# PL-N823-01_Analog_Breakout.net
KiCad netlist of a schematic drawn in EAGLE
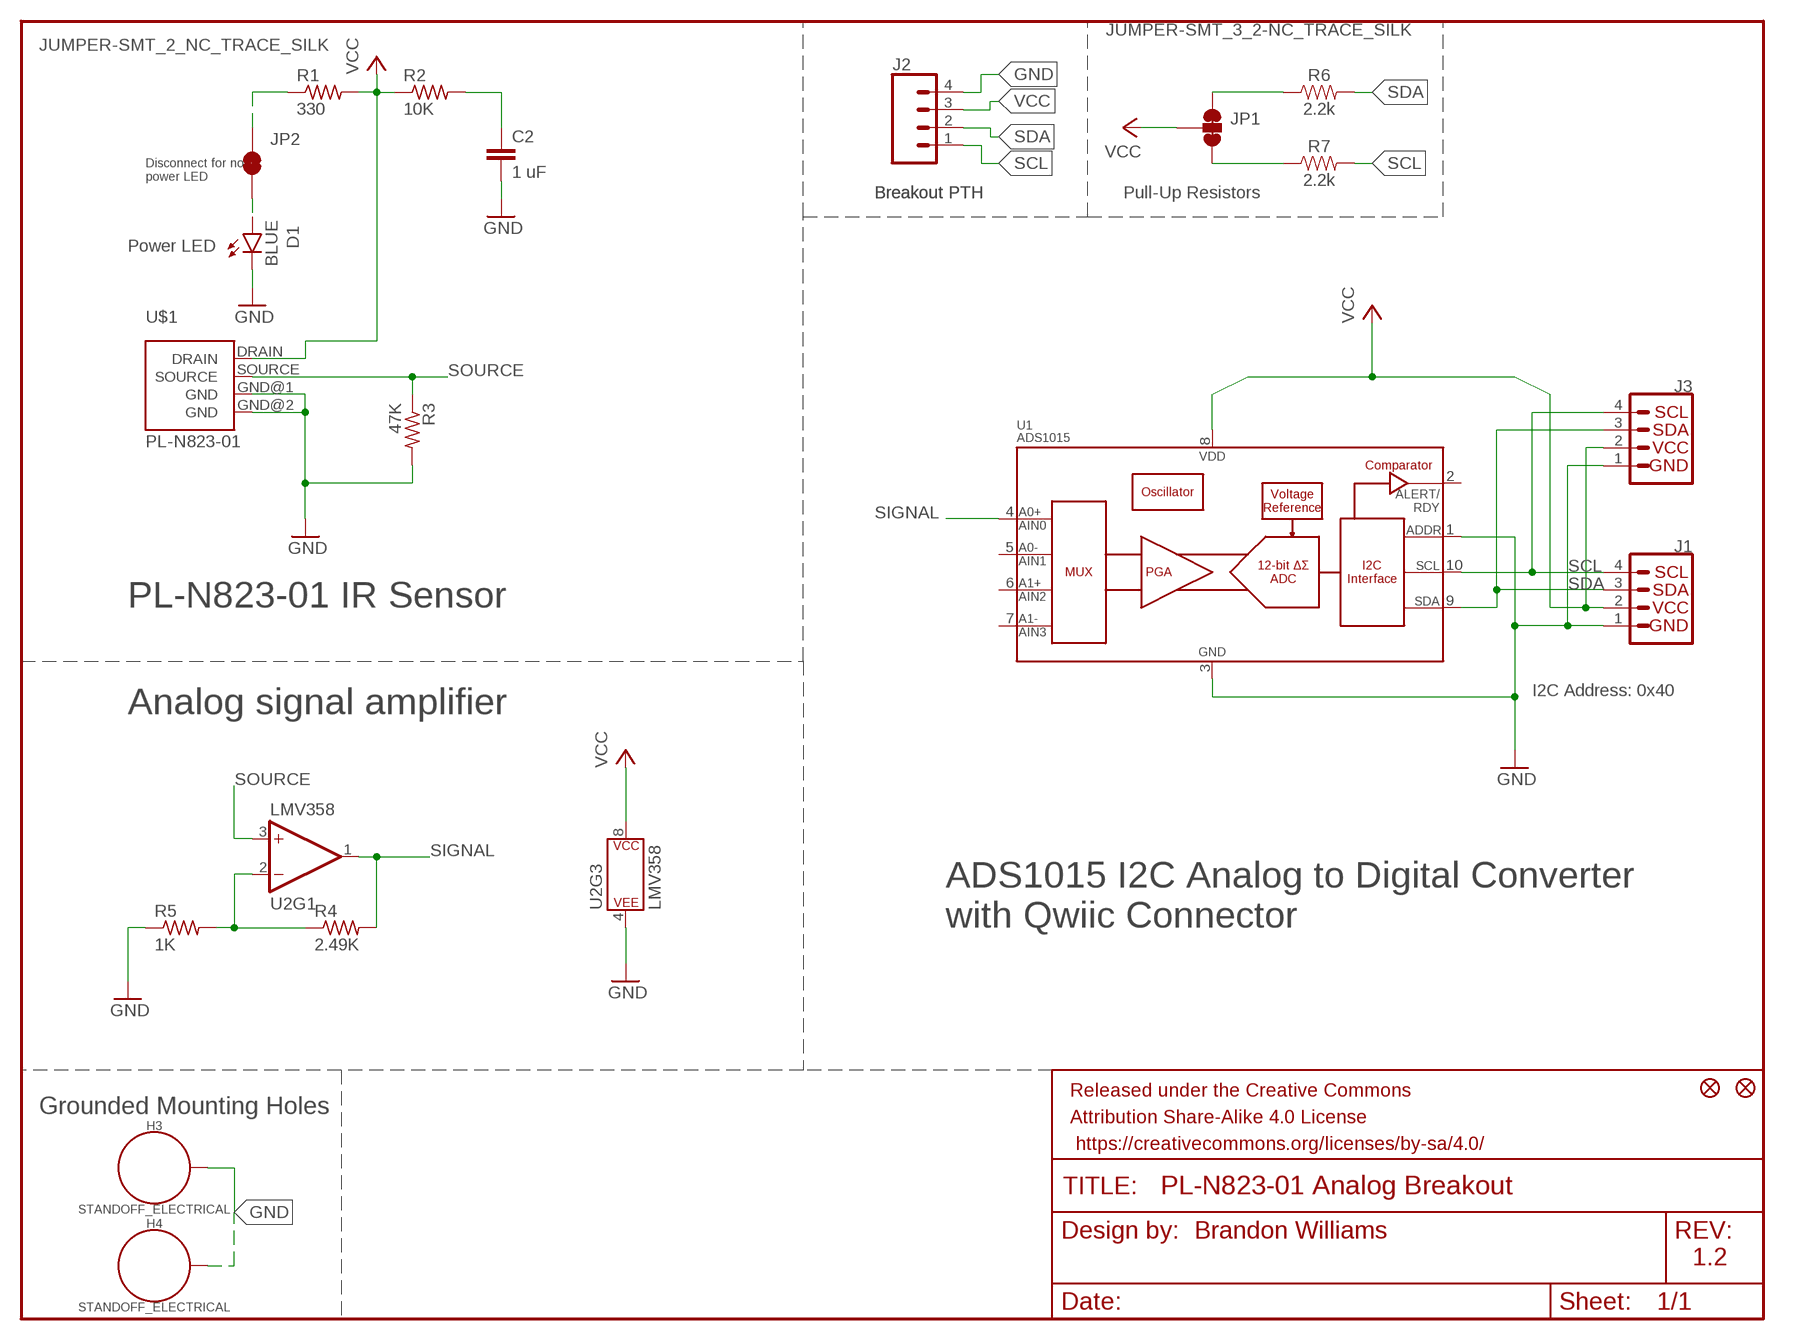
[diagram p0: schematic, sheet 1]

(export (version "E")
  (design (tool "Eeschema 10.0.6"))
  (components
    (comp (ref "C2")
      (value "1 uF")
      (footprint "eagle-import:C0603")
      (libsource (lib "eagle-import") (part "C-EUC0603"))
    )
    (comp (ref "D1")
      (value "BLUE")
      (footprint "eagle-import:LED-0603")
      (libsource (lib "eagle-import") (part "LED-BLUE0603"))
    )
    (comp (ref "FD1")
      (value "FIDUCIALUFIDUCIAL")
      (footprint "eagle-import:FIDUCIAL-MICRO")
      (libsource (lib "eagle-import") (part "FIDUCIALUFIDUCIAL"))
    )
    (comp (ref "FD2")
      (value "FIDUCIALUFIDUCIAL")
      (footprint "eagle-import:FIDUCIAL-MICRO")
      (libsource (lib "eagle-import") (part "FIDUCIALUFIDUCIAL"))
    )
    (comp (ref "FRAME1")
      (value "FRAME-LETTERNO_PACKAGE")
      (footprint "eagle-import:DUMMY")
      (fields (field (name "DESIGNER") "Nobody"))
      (libsource (lib "eagle-import") (part "FRAME-LETTERNO_PACKAGE"))
    )
    (comp (ref "H3")
      (value "STANDOFF_ELECTRICAL")
      (footprint "eagle-import:STANDOFF-ELECTRICAL")
      (libsource (lib "eagle-import") (part "STANDOFF_ELECTRICAL"))
    )
    (comp (ref "H4")
      (value "STANDOFF_ELECTRICAL")
      (footprint "eagle-import:STANDOFF-ELECTRICAL")
      (libsource (lib "eagle-import") (part "STANDOFF_ELECTRICAL"))
    )
    (comp (ref "J1")
      (value "QWIIC_CONNECTORJS-1MM")
      (footprint "eagle-import:1X04_1MM_RA")
      (libsource (lib "eagle-import") (part "QWIIC_CONNECTORJS-1MM"))
    )
    (comp (ref "J2")
      (value "CONN_041X04_NO_SILK")
      (footprint "eagle-import:1X04_NO_SILK")
      (libsource (lib "eagle-import") (part "CONN_041X04_NO_SILK"))
    )
    (comp (ref "J3")
      (value "QWIIC_CONNECTORJS-1MM")
      (footprint "eagle-import:1X04_1MM_RA")
      (libsource (lib "eagle-import") (part "QWIIC_CONNECTORJS-1MM"))
    )
    (comp (ref "JP1")
      (value "JUMPER-SMT_3_2-NC_TRACE_SILK")
      (footprint "eagle-import:SMT-JUMPER_3_2-NC_TRACE_SILK")
      (libsource (lib "eagle-import") (part "JUMPER-SMT_3_2-NC_TRACE_SILK"))
    )
    (comp (ref "JP2")
      (value "JUMPER-SMT_2_NC_TRACE_SILK")
      (footprint "eagle-import:SMT-JUMPER_2_NC_TRACE_SILK")
      (libsource (lib "eagle-import") (part "JUMPER-SMT_2_NC_TRACE_SILK"))
    )
    (comp (ref "R1")
      (value "330")
      (footprint "eagle-import:R0603")
      (libsource (lib "eagle-import") (part "R-US_R0603"))
    )
    (comp (ref "R2")
      (value "10K")
      (footprint "eagle-import:R0603")
      (libsource (lib "eagle-import") (part "R-US_R0603"))
    )
    (comp (ref "R3")
      (value "47K")
      (footprint "eagle-import:R0603")
      (libsource (lib "eagle-import") (part "R-US_R0603"))
    )
    (comp (ref "R4")
      (value "2.49K")
      (footprint "eagle-import:R0603")
      (libsource (lib "eagle-import") (part "R-US_R0603"))
    )
    (comp (ref "R5")
      (value "1K")
      (footprint "eagle-import:R0603")
      (libsource (lib "eagle-import") (part "R-US_R0603"))
    )
    (comp (ref "R6")
      (value "2.2k")
      (footprint "eagle-import:0603")
      (libsource (lib "eagle-import") (part "2.2KOHM-0603-1/10W-1%"))
    )
    (comp (ref "R7")
      (value "2.2k")
      (footprint "eagle-import:0603")
      (libsource (lib "eagle-import") (part "2.2KOHM-0603-1/10W-1%"))
    )
    (comp (ref "U$1")
      (value "PL-N823-01")
      (footprint "eagle-import:PL-N823-01")
      (libsource (lib "eagle-import") (part "PL-N823-01"))
    )
    (comp (ref "U1")
      (value "ADS1015")
      (footprint "eagle-import:MSOP10")
      (libsource (lib "eagle-import") (part "ADS1015"))
    )
    (comp (ref "U2")
      (value "LMV358")
      (footprint "eagle-import:SO08")
      (libsource (lib "eagle-import") (part "LMV358SOIC"))
    )
  )
  (nets
    (net (code "1") (name "/SIGNAL") (class "Default")
      (node (ref "R4") (pin "2") (pinfunction "2_2") (pintype "passive"))
      (node (ref "U1") (pin "4") (pinfunction "AIN0_4") (pintype "bidirectional"))
      (node (ref "U2") (pin "1") (pinfunction "OUT_1") (pintype "output"))
    )
    (net (code "2") (name "/SOURCE") (class "Default")
      (node (ref "R3") (pin "1") (pinfunction "1_1") (pintype "passive"))
      (node (ref "U$1") (pin "SOURCE") (pinfunction "SOURCE_SOURCE") (pintype "output"))
      (node (ref "U2") (pin "3") (pinfunction "+IN_3") (pintype "input"))
    )
    (net (code "3") (name "GND") (class "Default")
      (node (ref "C2") (pin "2") (pinfunction "2_2") (pintype "passive"))
      (node (ref "D1") (pin "C") (pinfunction "C_C") (pintype "passive"))
      (node (ref "H3") (pin "P1") (pinfunction "P$1_P1") (pintype "bidirectional"))
      (node (ref "H4") (pin "P1") (pinfunction "P$1_P1") (pintype "bidirectional"))
      (node (ref "J1") (pin "1") (pinfunction "GND_1") (pintype "power_in"))
      (node (ref "J2") (pin "4") (pinfunction "4_4") (pintype "passive"))
      (node (ref "J3") (pin "1") (pinfunction "GND_1") (pintype "power_in"))
      (node (ref "R3") (pin "2") (pinfunction "2_2") (pintype "passive"))
      (node (ref "R5") (pin "1") (pinfunction "1_1") (pintype "passive"))
      (node (ref "U$1") (pin "GND@1") (pinfunction "GND_GND@1") (pintype "power_in"))
      (node (ref "U$1") (pin "GND@2") (pinfunction "GND_GND@2") (pintype "power_in"))
      (node (ref "U1") (pin "1") (pinfunction "ADDR_1") (pintype "bidirectional"))
      (node (ref "U1") (pin "3") (pinfunction "VSS_3") (pintype "bidirectional"))
      (node (ref "U2") (pin "4") (pinfunction "P$V-_4") (pintype "bidirectional"))
    )
    (net (code "4") (name "Net-(C2-Pad1)") (class "Default")
      (node (ref "C2") (pin "1") (pinfunction "1_1") (pintype "passive"))
      (node (ref "R2") (pin "2") (pinfunction "2_2") (pintype "passive"))
    )
    (net (code "5") (name "Net-(D1-PadA)") (class "Default")
      (node (ref "D1") (pin "A") (pinfunction "A_A") (pintype "passive"))
      (node (ref "JP2") (pin "2") (pinfunction "2_2") (pintype "passive"))
    )
    (net (code "6") (name "Net-(JP1-Pad1)") (class "Default")
      (node (ref "JP1") (pin "1") (pinfunction "1_1") (pintype "passive"))
      (node (ref "R6") (pin "1") (pinfunction "1_1") (pintype "passive"))
    )
    (net (code "7") (name "Net-(JP1-Pad3)") (class "Default")
      (node (ref "JP1") (pin "3") (pinfunction "3_3") (pintype "passive"))
      (node (ref "R7") (pin "1") (pinfunction "1_1") (pintype "passive"))
    )
    (net (code "8") (name "Net-(JP2-Pad1)") (class "Default")
      (node (ref "JP2") (pin "1") (pinfunction "1_1") (pintype "passive"))
      (node (ref "R1") (pin "1") (pinfunction "1_1") (pintype "passive"))
    )
    (net (code "9") (name "Net-(U2A--IN)") (class "Default")
      (node (ref "R4") (pin "1") (pinfunction "1_1") (pintype "passive"))
      (node (ref "R5") (pin "2") (pinfunction "2_2") (pintype "passive"))
      (node (ref "U2") (pin "2") (pinfunction "-IN_2") (pintype "input"))
    )
    (net (code "10") (name "SCL") (class "Default")
      (node (ref "J1") (pin "4") (pinfunction "SCL_4") (pintype "passive"))
      (node (ref "J2") (pin "1") (pinfunction "1_1") (pintype "passive"))
      (node (ref "J3") (pin "4") (pinfunction "SCL_4") (pintype "passive"))
      (node (ref "R7") (pin "2") (pinfunction "2_2") (pintype "passive"))
      (node (ref "U1") (pin "10") (pinfunction "SCL_10") (pintype "bidirectional"))
    )
    (net (code "11") (name "SDA") (class "Default")
      (node (ref "J1") (pin "3") (pinfunction "SDA_3") (pintype "passive"))
      (node (ref "J2") (pin "2") (pinfunction "2_2") (pintype "passive"))
      (node (ref "J3") (pin "3") (pinfunction "SDA_3") (pintype "passive"))
      (node (ref "R6") (pin "2") (pinfunction "2_2") (pintype "passive"))
      (node (ref "U1") (pin "9") (pinfunction "SDA_9") (pintype "bidirectional"))
    )
    (net (code "12") (name "VCC") (class "Default")
      (node (ref "J1") (pin "2") (pinfunction "VCC_2") (pintype "power_in"))
      (node (ref "J2") (pin "3") (pinfunction "3_3") (pintype "passive"))
      (node (ref "J3") (pin "2") (pinfunction "VCC_2") (pintype "power_in"))
      (node (ref "JP1") (pin "2") (pinfunction "2_2") (pintype "passive"))
      (node (ref "R1") (pin "2") (pinfunction "2_2") (pintype "passive"))
      (node (ref "R2") (pin "1") (pinfunction "1_1") (pintype "passive"))
      (node (ref "U$1") (pin "DRAIN") (pinfunction "DRAIN_DRAIN") (pintype "input"))
      (node (ref "U1") (pin "8") (pinfunction "VDD_8") (pintype "bidirectional"))
      (node (ref "U2") (pin "8") (pinfunction "P$V+_8") (pintype "bidirectional"))
    )
    (net (code "13") (name "unconnected-(U1-AIN1-Pad5)") (class "Default")
      (node (ref "U1") (pin "5") (pinfunction "AIN1_5") (pintype "bidirectional"))
    )
    (net (code "14") (name "unconnected-(U1-AIN2-Pad6)") (class "Default")
      (node (ref "U1") (pin "6") (pinfunction "AIN2_6") (pintype "bidirectional"))
    )
    (net (code "15") (name "unconnected-(U1-AIN3-Pad7)") (class "Default")
      (node (ref "U1") (pin "7") (pinfunction "AIN3_7") (pintype "bidirectional"))
    )
    (net (code "16") (name "unconnected-(U1-ALERT{slash}RDY-Pad2)") (class "Default")
      (node (ref "U1") (pin "2") (pinfunction "ALERT/RDY_2") (pintype "bidirectional"))
    )
  )
)
